# CP2102.net
KiCad netlist of a schematic drawn in Altium Designer
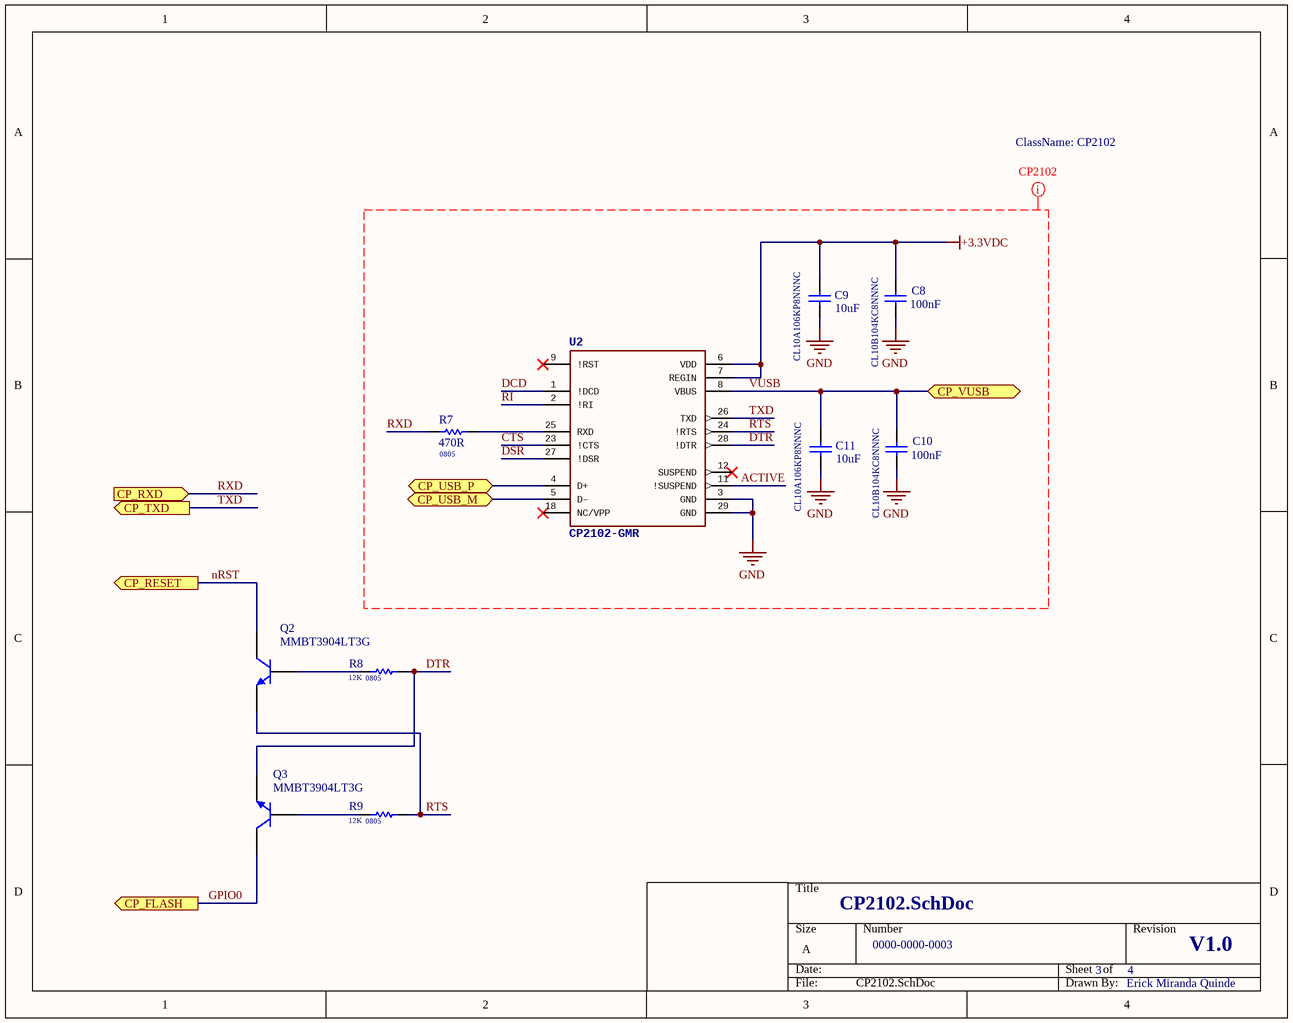
[diagram p0: CP2102.SchDoc]

(export (version "E")
  (design (tool "Eeschema 10.0.6"))
  (components
    (comp (ref "C8")
      (value "CL10B104KC8NNNC")
      (footprint "C0603C104K5RACTU")
      (fields (field (name "ALTIUM_VALUE") "100nF") (field (name "LCSC PART") "C15725"))
      (libsource (lib "IDETEC LIB") (part "Cap 100nF (0603)"))
    )
    (comp (ref "C9")
      (value "CL10A106KP8NNNC")
      (footprint "C0603C104K5RACTU")
      (fields (field (name "ALTIUM_VALUE") "10uF") (field (name "LCSC PART") "C19702"))
      (libsource (lib "IDETEC LIB") (part "Cap 100nF (0603)"))
    )
    (comp (ref "C10")
      (value "CL10B104KC8NNNC")
      (footprint "C0603C104K5RACTU")
      (fields (field (name "ALTIUM_VALUE") "100nF") (field (name "LCSC PART") "C15725"))
      (libsource (lib "IDETEC LIB") (part "Cap 100nF (0603)"))
    )
    (comp (ref "C11")
      (value "CL10A106KP8NNNC")
      (footprint "C0603C104K5RACTU")
      (fields (field (name "ALTIUM_VALUE") "10uF") (field (name "LCSC PART") "C19702"))
      (libsource (lib "IDETEC LIB") (part "Cap 100nF (0603)"))
    )
    (comp (ref "Q2")
      (value "MMBT3904LT3G")
      (footprint "SOT-23-TT3_N")
      (fields (field (name "LCSC PART") "C150052"))
      (libsource (lib "IDETEC LIB") (part "2N3904"))
    )
    (comp (ref "Q3")
      (value "MMBT3904LT3G")
      (footprint "SOT-23-TT3_N")
      (fields (field (name "LCSC PART") "C150052"))
      (libsource (lib "IDETEC LIB") (part "2N3904"))
    )
    (comp (ref "R7")
      (value "470R")
      (footprint "RES-0805")
      (description "Resistor")
      (fields
        (field (name "PACKAGE") "0805")
        (field (name "LCSC PART") "C17710")
        (field (name "Comment") "0805W8F4700T5E")
        (field (name "PUBLISHER") "Altium Limited")
      )
      (libsource (lib "IDETEC LIB") (part "Resistor"))
    )
    (comp (ref "R8")
      (value "12K")
      (footprint "RES-0805")
      (description "Resistor")
      (fields
        (field (name "PACKAGE") "0805")
        (field (name "LCSC PART") "C17444")
        (field (name "Comment") "0805W8F1202T5E")
        (field (name "PUBLISHER") "Altium Limited")
      )
      (libsource (lib "IDETEC LIB") (part "Resistor"))
    )
    (comp (ref "R9")
      (value "12K")
      (footprint "RES-0805")
      (description "Resistor")
      (fields
        (field (name "PACKAGE") "0805")
        (field (name "LCSC PART") "C17444")
        (field (name "Comment") "0805W8F1202T5E")
        (field (name "PUBLISHER") "Altium Limited")
      )
      (libsource (lib "IDETEC LIB") (part "Resistor"))
    )
    (comp (ref "U2")
      (value "CP2102-GMR")
      (footprint "QFN50P500X500X100-29N")
      (fields (field (name "MF") "Silicon Labs") (field (name "LCSC PART") "C6568"))
      (libsource (lib "CP2102-GM") (part "CP2102-GM"))
    )
  )
  (nets
    (net (code "1") (name "+3.3VDC") (class "Default")
      (node (ref "C8") (pin "2") (pinfunction "2_2") (pintype "passive"))
      (node (ref "C9") (pin "2") (pinfunction "2_2") (pintype "passive"))
      (node (ref "U2") (pin "6") (pinfunction "VDD_6") (pintype "power_in"))
      (node (ref "U2") (pin "7") (pinfunction "REGIN_7") (pintype "power_in"))
    )
    (net (code "2") (name "/ACTIVE") (class "Default")
      (node (ref "U2") (pin "11") (pinfunction "!SUSPEND_11") (pintype "output"))
    )
    (net (code "3") (name "/CP_USB_M") (class "Default")
      (node (ref "U2") (pin "5") (pinfunction "D–_5") (pintype "passive"))
    )
    (net (code "4") (name "/CP_USB_P") (class "Default")
      (node (ref "U2") (pin "4") (pinfunction "D+_4") (pintype "passive"))
    )
    (net (code "5") (name "/CTS") (class "Default")
      (node (ref "U2") (pin "23") (pinfunction "!CTS_23") (pintype "passive"))
    )
    (net (code "6") (name "/DCD") (class "Default")
      (node (ref "U2") (pin "1") (pinfunction "!DCD_1") (pintype "passive"))
    )
    (net (code "7") (name "/DSR") (class "Default")
      (node (ref "U2") (pin "27") (pinfunction "!DSR_27") (pintype "passive"))
    )
    (net (code "8") (name "/DTR") (class "Default")
      (node (ref "Q3") (pin "2") (pinfunction "E_2") (pintype "passive"))
      (node (ref "R8") (pin "2") (pinfunction "2_2") (pintype "passive"))
      (node (ref "U2") (pin "28") (pinfunction "!DTR_28") (pintype "output"))
    )
    (net (code "9") (name "/GPIO0") (class "Default")
      (node (ref "Q3") (pin "3") (pinfunction "C_3") (pintype "passive"))
    )
    (net (code "10") (name "/RI") (class "Default")
      (node (ref "U2") (pin "2") (pinfunction "!RI_2") (pintype "passive"))
    )
    (net (code "11") (name "/RTS") (class "Default")
      (node (ref "Q2") (pin "2") (pinfunction "E_2") (pintype "passive"))
      (node (ref "R9") (pin "2") (pinfunction "2_2") (pintype "passive"))
      (node (ref "U2") (pin "24") (pinfunction "!RTS_24") (pintype "output"))
    )
    (net (code "12") (name "/RXD") (class "Default")
      (node (ref "R7") (pin "1") (pinfunction "1_1") (pintype "passive"))
    )
    (net (code "13") (name "/TXD") (class "Default")
      (node (ref "U2") (pin "26") (pinfunction "TXD_26") (pintype "output"))
    )
    (net (code "14") (name "/VUSB") (class "Default")
      (node (ref "C10") (pin "2") (pinfunction "2_2") (pintype "passive"))
      (node (ref "C11") (pin "2") (pinfunction "2_2") (pintype "passive"))
      (node (ref "U2") (pin "8") (pinfunction "VBUS_8") (pintype "power_in"))
    )
    (net (code "15") (name "/nRST") (class "Default")
      (node (ref "Q2") (pin "3") (pinfunction "C_3") (pintype "passive"))
    )
    (net (code "16") (name "GND") (class "Default")
      (node (ref "C10") (pin "1") (pinfunction "1_1") (pintype "passive"))
      (node (ref "C11") (pin "1") (pinfunction "1_1") (pintype "passive"))
      (node (ref "C8") (pin "1") (pinfunction "1_1") (pintype "passive"))
      (node (ref "C9") (pin "1") (pinfunction "1_1") (pintype "passive"))
      (node (ref "U2") (pin "29") (pinfunction "GND_29") (pintype "power_in"))
      (node (ref "U2") (pin "3") (pinfunction "GND_3") (pintype "power_in"))
    )
    (net (code "17") (name "Net-(Q2-B)") (class "Default")
      (node (ref "Q2") (pin "1") (pinfunction "B_1") (pintype "passive"))
      (node (ref "R8") (pin "1") (pinfunction "1_1") (pintype "passive"))
    )
    (net (code "18") (name "Net-(Q3-B)") (class "Default")
      (node (ref "Q3") (pin "1") (pinfunction "B_1") (pintype "passive"))
      (node (ref "R9") (pin "1") (pinfunction "1_1") (pintype "passive"))
    )
    (net (code "19") (name "Net-(U2-RXD)") (class "Default")
      (node (ref "R7") (pin "2") (pinfunction "2_2") (pintype "passive"))
      (node (ref "U2") (pin "25") (pinfunction "RXD_25") (pintype "passive"))
    )
    (net (code "20") (name "unconnected-(U2-!RST-Pad9)") (class "Default")
      (node (ref "U2") (pin "9") (pinfunction "!RST_9") (pintype "passive+no_connect"))
    )
    (net (code "21") (name "unconnected-(U2-NC{slash}VPP-Pad18)") (class "Default")
      (node (ref "U2") (pin "18") (pinfunction "NC/VPP_18") (pintype "passive+no_connect"))
    )
    (net (code "22") (name "unconnected-(U2-SUSPEND-Pad12)") (class "Default")
      (node (ref "U2") (pin "12") (pinfunction "SUSPEND_12") (pintype "output+no_connect"))
    )
  )
)
